# board_A500_A4000_CD32.net
KiCad netlist of a schematic drawn in EAGLE
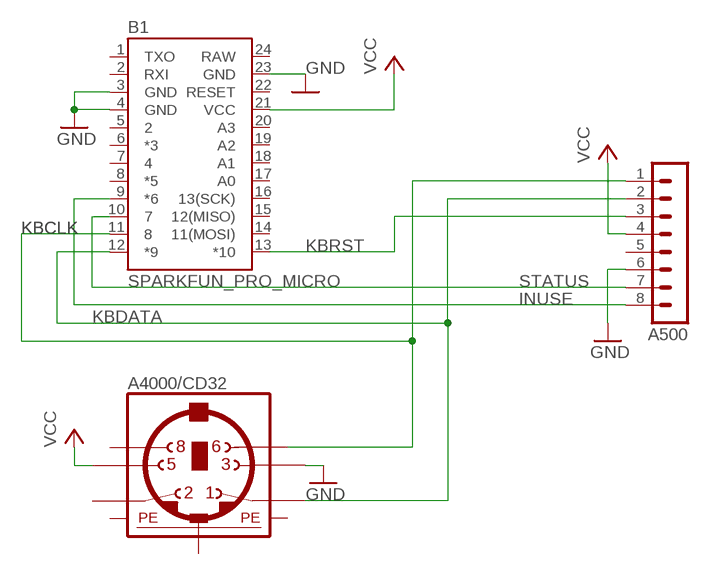
[diagram p0: schematic, sheet 1]

(export (version "E")
  (design (tool "Eeschema 10.0.6"))
  (components
    (comp (ref "A500")
      (value "MA08-1")
      (footprint "eagle-import:MA08-1")
      (libsource (lib "eagle-import") (part "MA08-1"))
    )
    (comp (ref "A4000/CD32")
      (value "MINI_DIN_6")
      (footprint "eagle-import:M_DIN6")
      (libsource (lib "eagle-import") (part "MINI_DIN_6"))
    )
    (comp (ref "B1")
      (value "SPARKFUN_PRO_MICRO")
      (footprint "eagle-import:SPARKFUN_PRO_MICRO")
      (libsource (lib "eagle-import") (part "SPARKFUN_PRO_MICRO"))
    )
  )
  (nets
    (net (code "1") (name "/INUSE") (class "Default")
      (node (ref "A500") (pin "8") (pinfunction "8_8") (pintype "passive"))
      (node (ref "B1") (pin "9") (pinfunction "*6_9") (pintype "bidirectional"))
    )
    (net (code "2") (name "/KBCLK") (class "Default")
      (node (ref "A4000/CD32") (pin "6") (pinfunction "6_6") (pintype "passive"))
      (node (ref "A500") (pin "1") (pinfunction "1_1") (pintype "passive"))
      (node (ref "B1") (pin "11") (pinfunction "8_11") (pintype "bidirectional"))
    )
    (net (code "3") (name "/KBDATA") (class "Default")
      (node (ref "A4000/CD32") (pin "1") (pinfunction "1_1") (pintype "passive"))
      (node (ref "A500") (pin "2") (pinfunction "2_2") (pintype "passive"))
      (node (ref "B1") (pin "12") (pinfunction "*9_12") (pintype "bidirectional"))
    )
    (net (code "4") (name "/KBRST") (class "Default")
      (node (ref "A500") (pin "3") (pinfunction "3_3") (pintype "passive"))
      (node (ref "B1") (pin "13") (pinfunction "*10_13") (pintype "bidirectional"))
    )
    (net (code "5") (name "/PE1") (class "Default")
      (node (ref "A4000/CD32") (pin "SH1") (pinfunction "PE1_SH1") (pintype "power_in"))
    )
    (net (code "6") (name "/PE2") (class "Default")
      (node (ref "A4000/CD32") (pin "SH2") (pinfunction "PE2_SH2") (pintype "power_in"))
    )
    (net (code "7") (name "/PE3") (class "Default")
      (node (ref "A4000/CD32") (pin "SH3") (pinfunction "PE3_SH3") (pintype "power_in"))
    )
    (net (code "8") (name "/RAW") (class "Default")
      (node (ref "B1") (pin "24") (pinfunction "RAW_24") (pintype "power_in"))
    )
    (net (code "9") (name "/STATUS") (class "Default")
      (node (ref "A500") (pin "7") (pinfunction "7_7") (pintype "passive"))
      (node (ref "B1") (pin "10") (pinfunction "7_10") (pintype "bidirectional"))
    )
    (net (code "10") (name "GND") (class "Default")
      (node (ref "A4000/CD32") (pin "3") (pinfunction "3_3") (pintype "passive"))
      (node (ref "A500") (pin "6") (pinfunction "6_6") (pintype "passive"))
      (node (ref "B1") (pin "23") (pinfunction "GND_23") (pintype "power_in"))
      (node (ref "B1") (pin "3") (pinfunction "GND_3") (pintype "power_in"))
      (node (ref "B1") (pin "4") (pinfunction "GND_4") (pintype "power_in"))
    )
    (net (code "11") (name "VCC") (class "Default")
      (node (ref "A4000/CD32") (pin "5") (pinfunction "5_5") (pintype "passive"))
      (node (ref "A500") (pin "4") (pinfunction "4_4") (pintype "passive"))
      (node (ref "B1") (pin "21") (pinfunction "VCC_21") (pintype "power_in"))
    )
    (net (code "12") (name "unconnected-(A500-Pad5)") (class "Default")
      (node (ref "A500") (pin "5") (pinfunction "5_5") (pintype "passive"))
    )
    (net (code "13") (name "unconnected-(A4000/CD32-Pad2)") (class "Default")
      (node (ref "A4000/CD32") (pin "2") (pinfunction "2_2") (pintype "passive"))
    )
    (net (code "14") (name "unconnected-(A4000/CD32-Pad8)") (class "Default")
      (node (ref "A4000/CD32") (pin "8") (pinfunction "8_8") (pintype "passive"))
    )
    (net (code "15") (name "unconnected-(B1-*3-Pad6)") (class "Default")
      (node (ref "B1") (pin "6") (pinfunction "*3_6") (pintype "bidirectional"))
    )
    (net (code "16") (name "unconnected-(B1-*5-Pad8)") (class "Default")
      (node (ref "B1") (pin "8") (pinfunction "*5_8") (pintype "bidirectional"))
    )
    (net (code "17") (name "unconnected-(B1-2-Pad5)") (class "Default")
      (node (ref "B1") (pin "5") (pinfunction "2_5") (pintype "bidirectional"))
    )
    (net (code "18") (name "unconnected-(B1-4-Pad7)") (class "Default")
      (node (ref "B1") (pin "7") (pinfunction "4_7") (pintype "bidirectional"))
    )
    (net (code "19") (name "unconnected-(B1-11(MOSI)-Pad14)") (class "Default")
      (node (ref "B1") (pin "14") (pinfunction "11(MOSI)_14") (pintype "bidirectional"))
    )
    (net (code "20") (name "unconnected-(B1-12(MISO)-Pad15)") (class "Default")
      (node (ref "B1") (pin "15") (pinfunction "12(MISO)_15") (pintype "bidirectional"))
    )
    (net (code "21") (name "unconnected-(B1-13(SCK)-Pad16)") (class "Default")
      (node (ref "B1") (pin "16") (pinfunction "13(SCK)_16") (pintype "bidirectional"))
    )
    (net (code "22") (name "unconnected-(B1-A0-Pad17)") (class "Default")
      (node (ref "B1") (pin "17") (pinfunction "A0_17") (pintype "bidirectional"))
    )
    (net (code "23") (name "unconnected-(B1-A1-Pad18)") (class "Default")
      (node (ref "B1") (pin "18") (pinfunction "A1_18") (pintype "bidirectional"))
    )
    (net (code "24") (name "unconnected-(B1-A2-Pad19)") (class "Default")
      (node (ref "B1") (pin "19") (pinfunction "A2_19") (pintype "bidirectional"))
    )
    (net (code "25") (name "unconnected-(B1-A3-Pad20)") (class "Default")
      (node (ref "B1") (pin "20") (pinfunction "A3_20") (pintype "bidirectional"))
    )
    (net (code "26") (name "unconnected-(B1-RESET-Pad22)") (class "Default")
      (node (ref "B1") (pin "22") (pinfunction "RESET_22") (pintype "bidirectional"))
    )
    (net (code "27") (name "unconnected-(B1-RXI-Pad2)") (class "Default")
      (node (ref "B1") (pin "2") (pinfunction "RXI_2") (pintype "bidirectional"))
    )
    (net (code "28") (name "unconnected-(B1-TXO-Pad1)") (class "Default")
      (node (ref "B1") (pin "1") (pinfunction "TXO_1") (pintype "bidirectional"))
    )
  )
)
